# openSX70-dongle_SEEED_v5.net
KiCad netlist of a schematic drawn in EAGLE
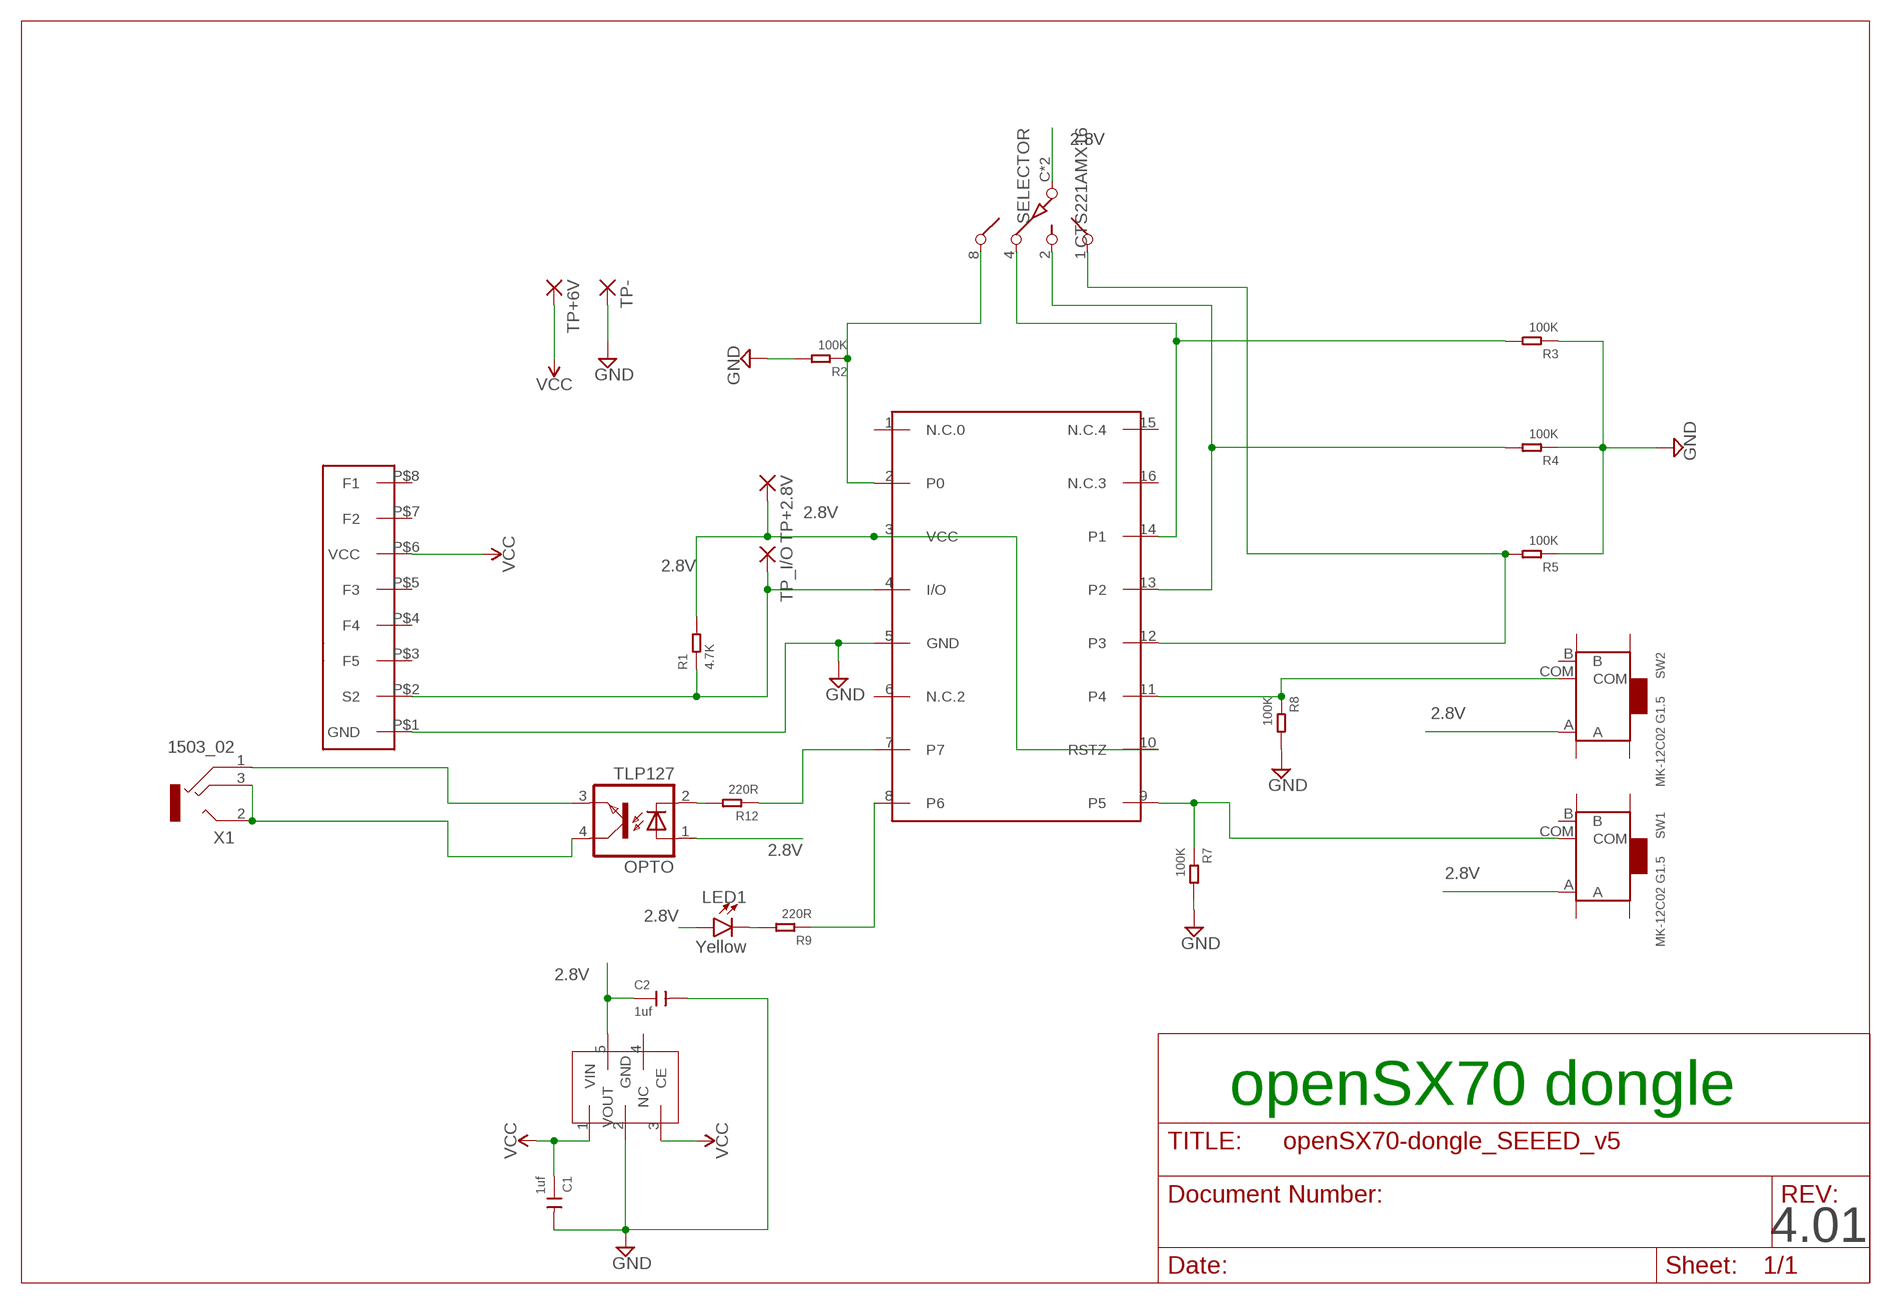
[diagram p0: schematic, sheet 1]

(export (version "E")
  (design (tool "Eeschema 10.0.6"))
  (components
    (comp (ref "C1")
      (value "1uf")
      (footprint "eagle-import:C0603")
      (fields (field (name "MPN") "CC0603KRX7R8BB105"))
      (libsource (lib "eagle-import") (part "CERAMIC-1UF-25V-10%-X7R(0603)"))
    )
    (comp (ref "C2")
      (value "1uf")
      (footprint "eagle-import:C0603")
      (fields (field (name "MPN") "CC0603KRX7R8BB105"))
      (libsource (lib "eagle-import") (part "CERAMIC-1UF-25V-10%-X7R(0603)"))
    )
    (comp (ref "DS2408")
      (value "DS2408")
      (footprint "eagle-import:SO16")
      (libsource (lib "eagle-import") (part "DS2408"))
    )
    (comp (ref "LED1")
      (value "Yellow")
      (footprint "eagle-import:LED-1206")
      (libsource (lib "eagle-import") (part "LED-YELLOWLILYPAD"))
    )
    (comp (ref "OPTO")
      (value "TLP127")
      (footprint "eagle-import:SO-4")
      (libsource (lib "eagle-import") (part "TLP127"))
    )
    (comp (ref "R1")
      (value "4.7K")
      (footprint "eagle-import:R0603")
      (fields (field (name "MPN") "RC0603JR-074K7L"))
      (libsource (lib "eagle-import") (part "SMD-RES-4.7K-5%-1/10W(0603)"))
    )
    (comp (ref "R2")
      (value "100K")
      (footprint "eagle-import:R0603")
      (fields (field (name "MPN") "RC0603FR-07100KL"))
      (libsource (lib "eagle-import") (part "SMD-RES-100K-1%-1/10W(0603)"))
    )
    (comp (ref "R3")
      (value "100K")
      (footprint "eagle-import:R0603")
      (fields (field (name "MPN") "RC0603FR-07100KL"))
      (libsource (lib "eagle-import") (part "SMD-RES-100K-1%-1/10W(0603)"))
    )
    (comp (ref "R4")
      (value "100K")
      (footprint "eagle-import:R0603")
      (fields (field (name "MPN") "RC0603FR-07100KL"))
      (libsource (lib "eagle-import") (part "SMD-RES-100K-1%-1/10W(0603)"))
    )
    (comp (ref "R5")
      (value "100K")
      (footprint "eagle-import:R0603")
      (fields (field (name "MPN") "RC0603FR-07100KL"))
      (libsource (lib "eagle-import") (part "SMD-RES-100K-1%-1/10W(0603)"))
    )
    (comp (ref "R7")
      (value "100K")
      (footprint "eagle-import:R0603")
      (fields (field (name "MPN") "RC0603FR-07100KL"))
      (libsource (lib "eagle-import") (part "SMD-RES-100K-1%-1/10W(0603)"))
    )
    (comp (ref "R8")
      (value "100K")
      (footprint "eagle-import:R0603")
      (fields (field (name "MPN") "RC0603FR-07100KL"))
      (libsource (lib "eagle-import") (part "SMD-RES-100K-1%-1/10W(0603)"))
    )
    (comp (ref "R9")
      (value "220R")
      (footprint "eagle-import:R0603")
      (fields (field (name "MPN") "RC0603JR-07220RL"))
      (libsource (lib "eagle-import") (part "SMD-RES-220R-5%-1/10W(0603)"))
    )
    (comp (ref "R12")
      (value "220R")
      (footprint "eagle-import:R0603")
      (fields (field (name "MPN") "RC0603JR-07220RL"))
      (libsource (lib "eagle-import") (part "SMD-RES-220R-5%-1/10W(0603)"))
    )
    (comp (ref "REG")
      (value "NCP4688")
      (footprint "eagle-import:SOT-23-5")
      (libsource (lib "eagle-import") (part "NCP4688"))
    )
    (comp (ref "SELECTOR")
      (value "CTS221AMX16")
      (footprint "eagle-import:CTS221AMX16")
      (libsource (lib "eagle-import") (part "CTS221AMX16"))
    )
    (comp (ref "SW1")
      (value "MK-12C02 G1.5")
      (footprint "eagle-import:SW7-SMD-L6.7X2.7X3.2MM")
      (libsource (lib "eagle-import") (part "SMD-TOGGLE-SWITCH-ON-ON(3+4P-6.7X2.7MM)"))
    )
    (comp (ref "SW2")
      (value "MK-12C02 G1.5")
      (footprint "eagle-import:SW7-SMD-L6.7X2.7X3.2MM")
      (libsource (lib "eagle-import") (part "SMD-TOGGLE-SWITCH-ON-ON(3+4P-6.7X2.7MM)"))
    )
    (comp (ref "TP+2.8V")
      (value "SMD2")
      (footprint "eagle-import:SMD1,27-2,54")
      (libsource (lib "eagle-import") (part "SMD2"))
    )
    (comp (ref "TP+6V")
      (value "SMD2")
      (footprint "eagle-import:SMD1,27-2,54")
      (libsource (lib "eagle-import") (part "SMD2"))
    )
    (comp (ref "TP-")
      (value "SMD2")
      (footprint "eagle-import:SMD1,27-2,54")
      (libsource (lib "eagle-import") (part "SMD2"))
    )
    (comp (ref "TP_I/O")
      (value "SMD2")
      (footprint "eagle-import:SMD1,27-2,54")
      (libsource (lib "eagle-import") (part "SMD2"))
    )
    (comp (ref "U$1")
      (value "FLASH-EDGE-CONNECTOR")
      (footprint "eagle-import:FLASH-EDGE-8")
      (libsource (lib "eagle-import") (part "FLASH-EDGE-CONNECTOR"))
    )
    (comp (ref "X1")
      (value "1503_02")
      (footprint "eagle-import:1503_02")
      (libsource (lib "eagle-import") (part "1503_02"))
    )
  )
  (nets
    (net (code "1") (name "/2.8V") (class "Default")
      (node (ref "C2") (pin "1") (pinfunction "1_1") (pintype "passive"))
      (node (ref "DS2408") (pin "10") (pinfunction "RSTZ_10") (pintype "bidirectional"))
      (node (ref "DS2408") (pin "3") (pinfunction "VCC_3") (pintype "bidirectional"))
      (node (ref "LED1") (pin "A") (pinfunction "A_A") (pintype "passive"))
      (node (ref "OPTO") (pin "1") (pinfunction "A_1") (pintype "passive"))
      (node (ref "R1") (pin "2") (pinfunction "2_2") (pintype "passive"))
      (node (ref "REG") (pin "5") (pinfunction "VOUT_5") (pintype "bidirectional"))
      (node (ref "SELECTOR") (pin "C") (pinfunction "C_C") (pintype "passive"))
      (node (ref "SELECTOR") (pin "C2") (pinfunction "C_C2") (pintype "passive"))
      (node (ref "SW1") (pin "A") (pinfunction "A_A") (pintype "bidirectional"))
      (node (ref "SW2") (pin "A") (pinfunction "A_A") (pintype "bidirectional"))
      (node (ref "TP+2.8V") (pin "1") (pinfunction "P_1") (pintype "passive"))
    )
    (net (code "2") (name "GND") (class "Default")
      (node (ref "C1") (pin "2") (pinfunction "2_2") (pintype "passive"))
      (node (ref "C2") (pin "2") (pinfunction "2_2") (pintype "passive"))
      (node (ref "DS2408") (pin "5") (pinfunction "GND_5") (pintype "bidirectional"))
      (node (ref "R2") (pin "2") (pinfunction "2_2") (pintype "passive"))
      (node (ref "R3") (pin "1") (pinfunction "1_1") (pintype "passive"))
      (node (ref "R4") (pin "1") (pinfunction "1_1") (pintype "passive"))
      (node (ref "R5") (pin "1") (pinfunction "1_1") (pintype "passive"))
      (node (ref "R7") (pin "2") (pinfunction "2_2") (pintype "passive"))
      (node (ref "R8") (pin "2") (pinfunction "2_2") (pintype "passive"))
      (node (ref "REG") (pin "2") (pinfunction "GND_2") (pintype "bidirectional"))
      (node (ref "TP-") (pin "1") (pinfunction "P_1") (pintype "passive"))
      (node (ref "U$1") (pin "P$1") (pinfunction "GND_P$1") (pintype "bidirectional"))
    )
    (net (code "3") (name "Net-(DS2408-I{slash}O)") (class "Default")
      (node (ref "DS2408") (pin "4") (pinfunction "I/O_4") (pintype "bidirectional"))
      (node (ref "R1") (pin "1") (pinfunction "1_1") (pintype "passive"))
      (node (ref "TP_I/O") (pin "1") (pinfunction "P_1") (pintype "passive"))
      (node (ref "U$1") (pin "P$2") (pinfunction "S2_P$2") (pintype "bidirectional"))
    )
    (net (code "4") (name "Net-(DS2408-P0)") (class "Default")
      (node (ref "DS2408") (pin "2") (pinfunction "P0_2") (pintype "bidirectional"))
      (node (ref "R2") (pin "1") (pinfunction "1_1") (pintype "passive"))
      (node (ref "SELECTOR") (pin "8") (pinfunction "8_8") (pintype "passive"))
    )
    (net (code "5") (name "Net-(DS2408-P1)") (class "Default")
      (node (ref "DS2408") (pin "14") (pinfunction "P1_14") (pintype "bidirectional"))
      (node (ref "R3") (pin "2") (pinfunction "2_2") (pintype "passive"))
      (node (ref "SELECTOR") (pin "4") (pinfunction "4_4") (pintype "passive"))
    )
    (net (code "6") (name "Net-(DS2408-P2)") (class "Default")
      (node (ref "DS2408") (pin "13") (pinfunction "P2_13") (pintype "bidirectional"))
      (node (ref "R4") (pin "2") (pinfunction "2_2") (pintype "passive"))
      (node (ref "SELECTOR") (pin "2") (pinfunction "2_2") (pintype "passive"))
    )
    (net (code "7") (name "Net-(DS2408-P3)") (class "Default")
      (node (ref "DS2408") (pin "12") (pinfunction "P3_12") (pintype "bidirectional"))
      (node (ref "R5") (pin "2") (pinfunction "2_2") (pintype "passive"))
      (node (ref "SELECTOR") (pin "1") (pinfunction "1_1") (pintype "passive"))
    )
    (net (code "8") (name "Net-(DS2408-P4)") (class "Default")
      (node (ref "DS2408") (pin "11") (pinfunction "P4_11") (pintype "bidirectional"))
      (node (ref "R8") (pin "1") (pinfunction "1_1") (pintype "passive"))
      (node (ref "SW2") (pin "COM") (pinfunction "COM_COM") (pintype "bidirectional"))
    )
    (net (code "9") (name "Net-(DS2408-P5)") (class "Default")
      (node (ref "DS2408") (pin "9") (pinfunction "P5_9") (pintype "bidirectional"))
      (node (ref "R7") (pin "1") (pinfunction "1_1") (pintype "passive"))
      (node (ref "SW1") (pin "COM") (pinfunction "COM_COM") (pintype "bidirectional"))
    )
    (net (code "10") (name "Net-(DS2408-P6)") (class "Default")
      (node (ref "DS2408") (pin "8") (pinfunction "P6_8") (pintype "bidirectional"))
      (node (ref "R9") (pin "1") (pinfunction "1_1") (pintype "passive"))
    )
    (net (code "11") (name "Net-(DS2408-P7)") (class "Default")
      (node (ref "DS2408") (pin "7") (pinfunction "P7_7") (pintype "bidirectional"))
      (node (ref "R12") (pin "1") (pinfunction "1_1") (pintype "passive"))
    )
    (net (code "12") (name "Net-(LED1-PadC)") (class "Default")
      (node (ref "LED1") (pin "C") (pinfunction "C_C") (pintype "passive"))
      (node (ref "R9") (pin "2") (pinfunction "2_2") (pintype "passive"))
    )
    (net (code "13") (name "Net-(OPTO-C)") (class "Default")
      (node (ref "OPTO") (pin "2") (pinfunction "C_2") (pintype "passive"))
      (node (ref "R12") (pin "2") (pinfunction "2_2") (pintype "passive"))
    )
    (net (code "14") (name "Net-(OPTO-COL)") (class "Default")
      (node (ref "OPTO") (pin "4") (pinfunction "COL_4") (pintype "passive"))
      (node (ref "X1") (pin "2") (pinfunction "2_2") (pintype "passive"))
      (node (ref "X1") (pin "3") (pinfunction "3_3") (pintype "passive"))
    )
    (net (code "15") (name "Net-(OPTO-EMIT)") (class "Default")
      (node (ref "OPTO") (pin "3") (pinfunction "EMIT_3") (pintype "passive"))
      (node (ref "X1") (pin "1") (pinfunction "1_1") (pintype "passive"))
    )
    (net (code "16") (name "VCC") (class "Default")
      (node (ref "C1") (pin "1") (pinfunction "1_1") (pintype "passive"))
      (node (ref "REG") (pin "1") (pinfunction "VIN_1") (pintype "bidirectional"))
      (node (ref "REG") (pin "3") (pinfunction "CE_3") (pintype "bidirectional"))
      (node (ref "TP+6V") (pin "1") (pinfunction "P_1") (pintype "passive"))
      (node (ref "U$1") (pin "P$6") (pinfunction "VCC_P$6") (pintype "bidirectional"))
    )
    (net (code "17") (name "unconnected-(DS2408-N.C.0-Pad1)") (class "Default")
      (node (ref "DS2408") (pin "1") (pinfunction "N.C.0_1") (pintype "bidirectional"))
    )
    (net (code "18") (name "unconnected-(DS2408-N.C.2-Pad6)") (class "Default")
      (node (ref "DS2408") (pin "6") (pinfunction "N.C.2_6") (pintype "bidirectional"))
    )
    (net (code "19") (name "unconnected-(DS2408-N.C.3-Pad16)") (class "Default")
      (node (ref "DS2408") (pin "16") (pinfunction "N.C.3_16") (pintype "bidirectional"))
    )
    (net (code "20") (name "unconnected-(DS2408-N.C.4-Pad15)") (class "Default")
      (node (ref "DS2408") (pin "15") (pinfunction "N.C.4_15") (pintype "bidirectional"))
    )
    (net (code "21") (name "unconnected-(REG-NC-Pad4)") (class "Default")
      (node (ref "REG") (pin "4") (pinfunction "NC_4") (pintype "bidirectional"))
    )
    (net (code "22") (name "unconnected-(SW1-PadB)") (class "Default")
      (node (ref "SW1") (pin "B") (pinfunction "B_B") (pintype "bidirectional"))
    )
    (net (code "23") (name "unconnected-(SW1-PadSS1)") (class "Default")
      (node (ref "SW1") (pin "SS1") (pinfunction "SS1_SS1") (pintype "bidirectional"))
    )
    (net (code "24") (name "unconnected-(SW1-PadSS2)") (class "Default")
      (node (ref "SW1") (pin "SS2") (pinfunction "SS2_SS2") (pintype "bidirectional"))
    )
    (net (code "25") (name "unconnected-(SW1-PadSS3)") (class "Default")
      (node (ref "SW1") (pin "SS3") (pinfunction "SS3_SS3") (pintype "bidirectional"))
    )
    (net (code "26") (name "unconnected-(SW1-PadSS4)") (class "Default")
      (node (ref "SW1") (pin "SS4") (pinfunction "SS4_SS4") (pintype "bidirectional"))
    )
    (net (code "27") (name "unconnected-(SW2-PadB)") (class "Default")
      (node (ref "SW2") (pin "B") (pinfunction "B_B") (pintype "bidirectional"))
    )
    (net (code "28") (name "unconnected-(SW2-PadSS1)") (class "Default")
      (node (ref "SW2") (pin "SS1") (pinfunction "SS1_SS1") (pintype "bidirectional"))
    )
    (net (code "29") (name "unconnected-(SW2-PadSS2)") (class "Default")
      (node (ref "SW2") (pin "SS2") (pinfunction "SS2_SS2") (pintype "bidirectional"))
    )
    (net (code "30") (name "unconnected-(SW2-PadSS3)") (class "Default")
      (node (ref "SW2") (pin "SS3") (pinfunction "SS3_SS3") (pintype "bidirectional"))
    )
    (net (code "31") (name "unconnected-(SW2-PadSS4)") (class "Default")
      (node (ref "SW2") (pin "SS4") (pinfunction "SS4_SS4") (pintype "bidirectional"))
    )
    (net (code "32") (name "unconnected-(U$1-F1-PadP$8)") (class "Default")
      (node (ref "U$1") (pin "P$8") (pinfunction "F1_P$8") (pintype "bidirectional"))
    )
    (net (code "33") (name "unconnected-(U$1-F2-PadP$7)") (class "Default")
      (node (ref "U$1") (pin "P$7") (pinfunction "F2_P$7") (pintype "bidirectional"))
    )
    (net (code "34") (name "unconnected-(U$1-F3-PadP$5)") (class "Default")
      (node (ref "U$1") (pin "P$5") (pinfunction "F3_P$5") (pintype "bidirectional"))
    )
    (net (code "35") (name "unconnected-(U$1-F4-PadP$4)") (class "Default")
      (node (ref "U$1") (pin "P$4") (pinfunction "F4_P$4") (pintype "bidirectional"))
    )
    (net (code "36") (name "unconnected-(U$1-F5-PadP$3)") (class "Default")
      (node (ref "U$1") (pin "P$3") (pinfunction "F5_P$3") (pintype "bidirectional"))
    )
    (net (code "37") (name "unconnected-(X1-2-Pad2@2)") (class "Default")
      (node (ref "X1") (pin "2@2") (pinfunction "2_2@2") (pintype "passive"))
    )
  )
)
